# esp-adapter.net
KiCad netlist of a schematic drawn in EAGLE
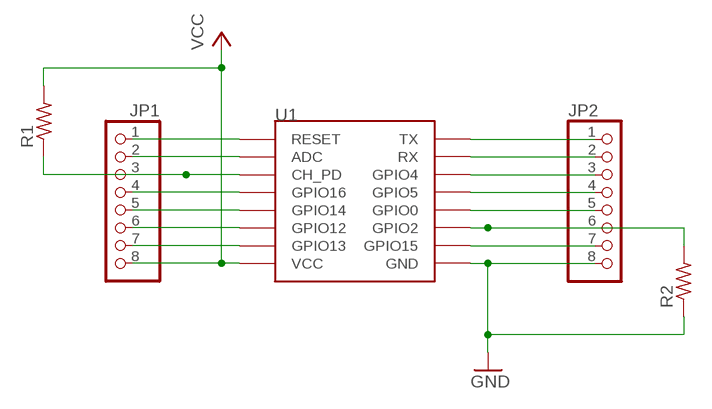
[diagram p0: schematic, sheet 1]

(export (version "E")
  (design (tool "Eeschema 10.0.6"))
  (components
    (comp (ref "JP1")
      (value "PINHD-1X8")
      (footprint "eagle-import:1X08")
      (libsource (lib "eagle-import") (part "PINHD-1X8"))
    )
    (comp (ref "JP2")
      (value "PINHD-1X8")
      (footprint "eagle-import:1X08")
      (libsource (lib "eagle-import") (part "PINHD-1X8"))
    )
    (comp (ref "R1")
      (value "R-US_R0805")
      (footprint "eagle-import:R0805")
      (libsource (lib "eagle-import") (part "R-US_R0805"))
    )
    (comp (ref "R2")
      (value "R-US_R0805")
      (footprint "eagle-import:R0805")
      (libsource (lib "eagle-import") (part "R-US_R0805"))
    )
    (comp (ref "U1")
      (value "ESP12SMD")
      (footprint "eagle-import:ESP12-SMD")
      (libsource (lib "eagle-import") (part "ESP12SMD"))
    )
  )
  (nets
    (net (code "1") (name "GND") (class "Default")
      (node (ref "JP2") (pin "8") (pinfunction "8_8") (pintype "passive"))
      (node (ref "R2") (pin "1") (pinfunction "1_1") (pintype "passive"))
      (node (ref "U1") (pin "GND") (pinfunction "GND_GND") (pintype "bidirectional"))
    )
    (net (code "2") (name "Net-(JP1-Pad1)") (class "Default")
      (node (ref "JP1") (pin "1") (pinfunction "1_1") (pintype "passive"))
      (node (ref "U1") (pin "RESET") (pinfunction "RESET_RESET") (pintype "bidirectional"))
    )
    (net (code "3") (name "Net-(JP1-Pad2)") (class "Default")
      (node (ref "JP1") (pin "2") (pinfunction "2_2") (pintype "passive"))
      (node (ref "U1") (pin "ADC") (pinfunction "ADC_ADC") (pintype "bidirectional"))
    )
    (net (code "4") (name "Net-(JP1-Pad3)") (class "Default")
      (node (ref "JP1") (pin "3") (pinfunction "3_3") (pintype "passive"))
      (node (ref "R1") (pin "1") (pinfunction "1_1") (pintype "passive"))
      (node (ref "U1") (pin "CH_PD") (pinfunction "CH_PD_CH_PD") (pintype "bidirectional"))
    )
    (net (code "5") (name "Net-(JP1-Pad4)") (class "Default")
      (node (ref "JP1") (pin "4") (pinfunction "4_4") (pintype "passive"))
      (node (ref "U1") (pin "GPIO16") (pinfunction "GPIO16_GPIO16") (pintype "bidirectional"))
    )
    (net (code "6") (name "Net-(JP1-Pad5)") (class "Default")
      (node (ref "JP1") (pin "5") (pinfunction "5_5") (pintype "passive"))
      (node (ref "U1") (pin "GPIO14") (pinfunction "GPIO14_GPIO14") (pintype "bidirectional"))
    )
    (net (code "7") (name "Net-(JP1-Pad6)") (class "Default")
      (node (ref "JP1") (pin "6") (pinfunction "6_6") (pintype "passive"))
      (node (ref "U1") (pin "GPIO12") (pinfunction "GPIO12_GPIO12") (pintype "bidirectional"))
    )
    (net (code "8") (name "Net-(JP1-Pad7)") (class "Default")
      (node (ref "JP1") (pin "7") (pinfunction "7_7") (pintype "passive"))
      (node (ref "U1") (pin "GPIO13") (pinfunction "GPIO13_GPIO13") (pintype "bidirectional"))
    )
    (net (code "9") (name "Net-(JP2-Pad3)") (class "Default")
      (node (ref "JP2") (pin "3") (pinfunction "3_3") (pintype "passive"))
      (node (ref "U1") (pin "GPIO4") (pinfunction "GPIO4_GPIO4") (pintype "bidirectional"))
    )
    (net (code "10") (name "Net-(JP2-Pad4)") (class "Default")
      (node (ref "JP2") (pin "4") (pinfunction "4_4") (pintype "passive"))
      (node (ref "U1") (pin "GPIO5") (pinfunction "GPIO5_GPIO5") (pintype "bidirectional"))
    )
    (net (code "11") (name "Net-(JP2-Pad5)") (class "Default")
      (node (ref "JP2") (pin "5") (pinfunction "5_5") (pintype "passive"))
      (node (ref "U1") (pin "GPIO0") (pinfunction "GPIO0_GPIO0") (pintype "bidirectional"))
    )
    (net (code "12") (name "Net-(JP2-Pad6)") (class "Default")
      (node (ref "JP2") (pin "6") (pinfunction "6_6") (pintype "passive"))
      (node (ref "R2") (pin "2") (pinfunction "2_2") (pintype "passive"))
      (node (ref "U1") (pin "GPIO2") (pinfunction "GPIO2_GPIO2") (pintype "bidirectional"))
    )
    (net (code "13") (name "Net-(JP2-Pad7)") (class "Default")
      (node (ref "JP2") (pin "7") (pinfunction "7_7") (pintype "passive"))
      (node (ref "U1") (pin "GPIO15") (pinfunction "GPIO15_GPIO15") (pintype "bidirectional"))
    )
    (net (code "14") (name "Net-(U1-RX)") (class "Default")
      (node (ref "JP2") (pin "2") (pinfunction "2_2") (pintype "passive"))
      (node (ref "U1") (pin "RXD0") (pinfunction "RX_RXD0") (pintype "bidirectional"))
    )
    (net (code "15") (name "Net-(U1-TX)") (class "Default")
      (node (ref "JP2") (pin "1") (pinfunction "1_1") (pintype "passive"))
      (node (ref "U1") (pin "TXD0") (pinfunction "TX_TXD0") (pintype "bidirectional"))
    )
    (net (code "16") (name "VCC") (class "Default")
      (node (ref "JP1") (pin "8") (pinfunction "8_8") (pintype "passive"))
      (node (ref "R1") (pin "2") (pinfunction "2_2") (pintype "passive"))
      (node (ref "U1") (pin "VCC") (pinfunction "VCC_VCC") (pintype "bidirectional"))
    )
  )
)
